# Domino_JTAG_SPI_No_Teardrop.net
KiCad netlist of a schematic drawn in EAGLE
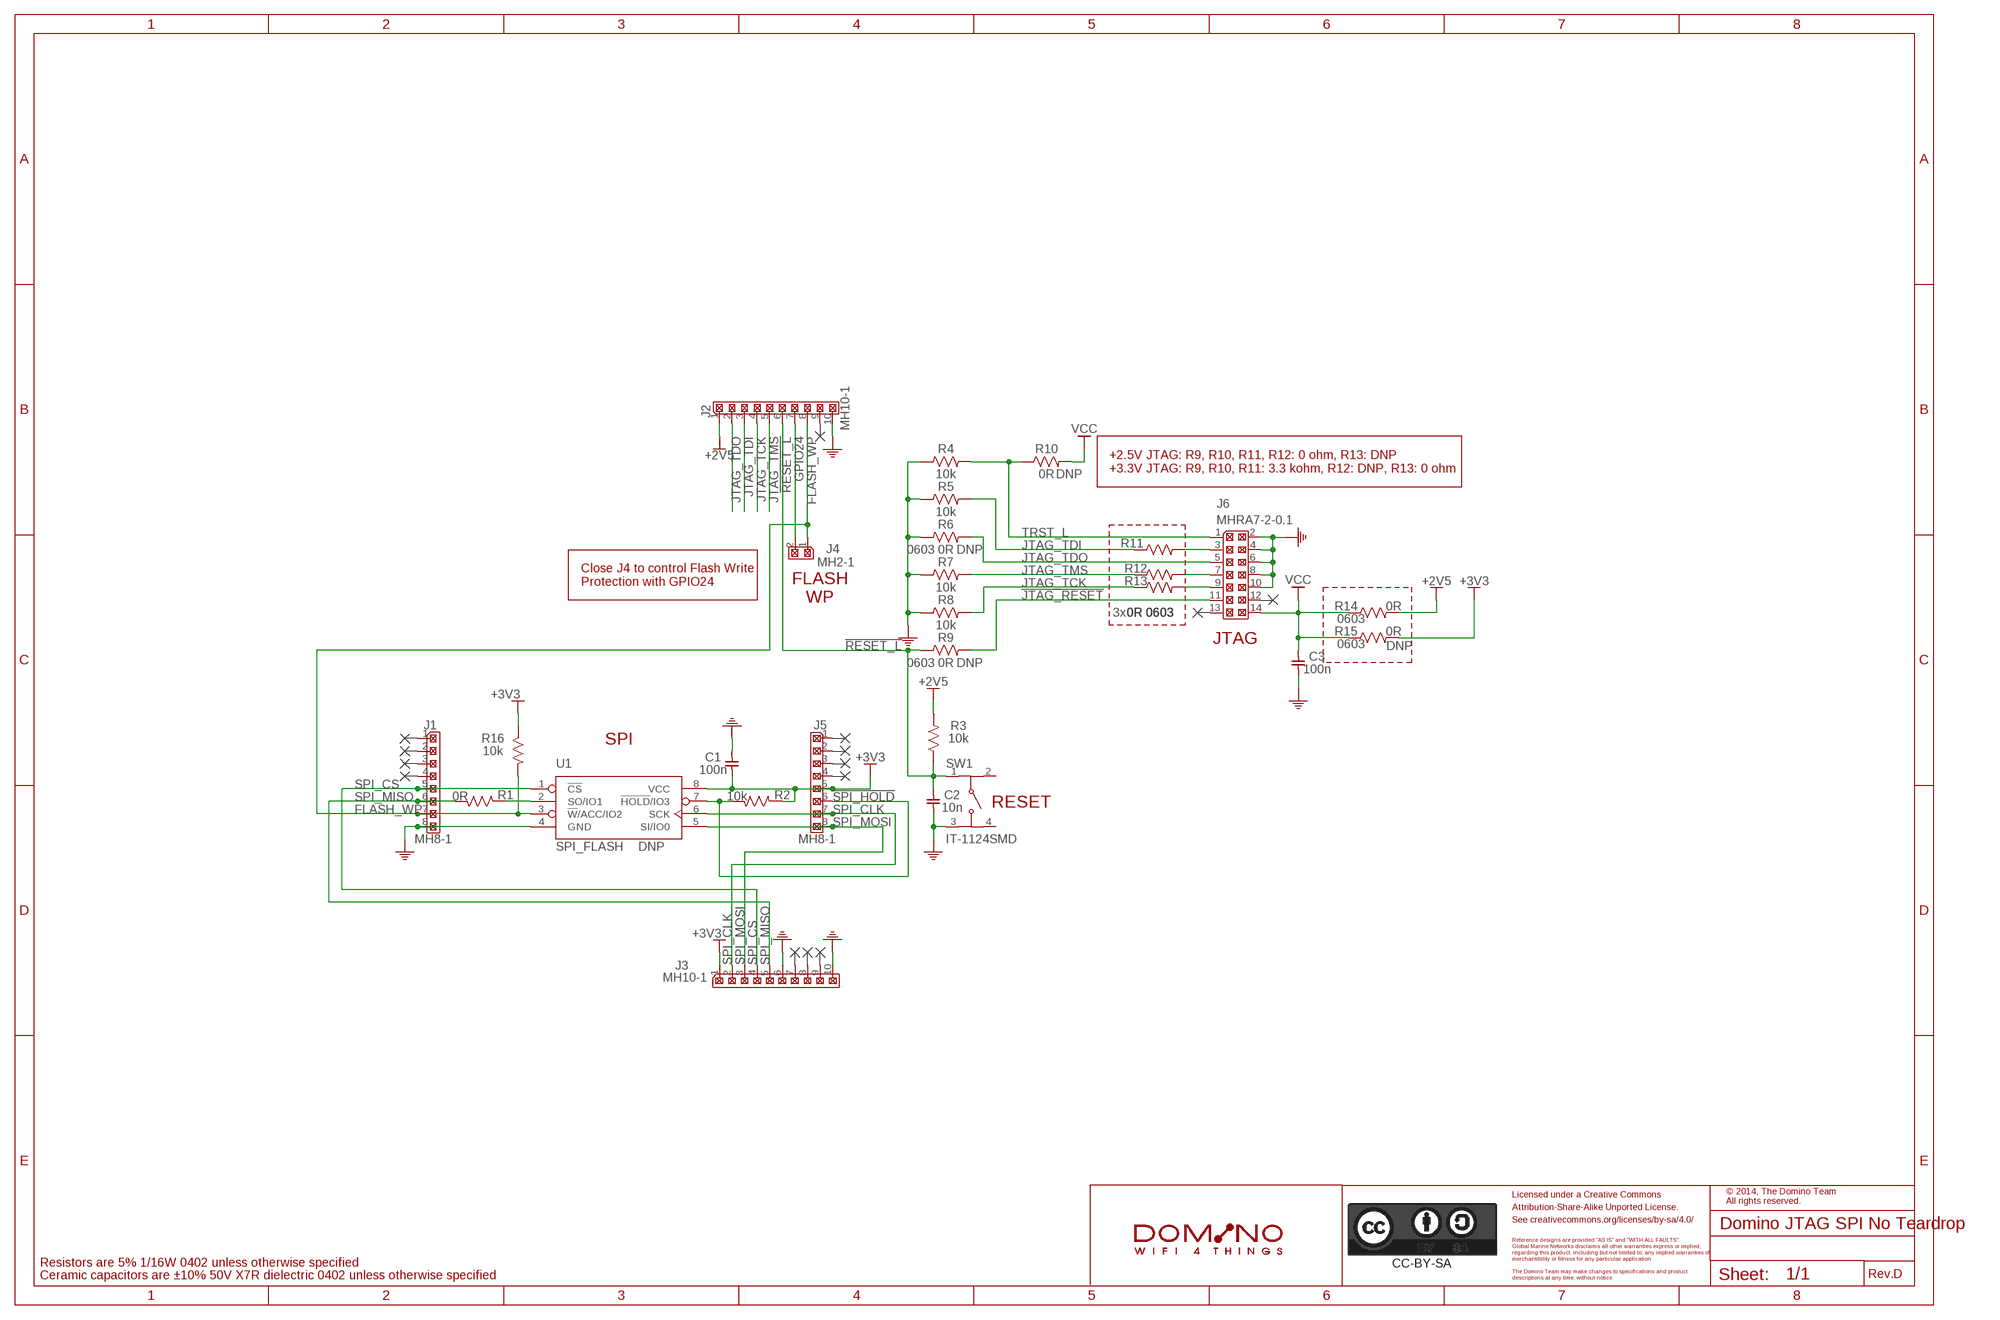
[diagram p0: schematic, sheet 1]

(export (version "E")
  (design (tool "Eeschema 10.0.6"))
  (components
    (comp (ref "C1")
      (value "100n")
      (footprint "eagle-import:C0402")
      (fields (field (name "PARTNO") "C0402_100n_X7R_10%_CER_50V"))
      (libsource (lib "eagle-import") (part "CAP_0402"))
    )
    (comp (ref "C2")
      (value "10n")
      (footprint "eagle-import:C0402")
      (fields (field (name "PARTNO") "C0402_10n_X7R_10%_CER_50V"))
      (libsource (lib "eagle-import") (part "CAP_0402"))
    )
    (comp (ref "C3")
      (value "100n")
      (footprint "eagle-import:C0402")
      (fields (field (name "PARTNO") "C0402_100n_X7R_10%_CER_50V"))
      (libsource (lib "eagle-import") (part "CAP_0402"))
    )
    (comp (ref "CC-BY-SA1")
      (value "CC-BY-SA_LOGO")
      (footprint "eagle-import:CC-BY-SA_LOGO")
      (libsource (lib "eagle-import") (part "CC-BY-SA_LOGO"))
    )
    (comp (ref "J1")
      (value "MH8-1")
      (footprint "eagle-import:MH8-1-0.1")
      (fields (field (name "PARTNO") "MH8-1-0.1"))
      (libsource (lib "eagle-import") (part "MH8-1"))
    )
    (comp (ref "J2")
      (value "MH10-1")
      (footprint "eagle-import:MH10-1-0.1")
      (fields (field (name "PARTNO") "MH10-1-0.1"))
      (libsource (lib "eagle-import") (part "MH10-1"))
    )
    (comp (ref "J3")
      (value "MH10-1")
      (footprint "eagle-import:MH10-1-0.1")
      (fields (field (name "PARTNO") "MH10-1-0.1"))
      (libsource (lib "eagle-import") (part "MH10-1"))
    )
    (comp (ref "J4")
      (value "MH2-1")
      (footprint "eagle-import:MH2-1-0.1")
      (fields (field (name "PARTNO") "MH2-1-0.1"))
      (libsource (lib "eagle-import") (part "MH2-1"))
    )
    (comp (ref "J5")
      (value "MH8-1")
      (footprint "eagle-import:MH8-1-0.1")
      (fields (field (name "PARTNO") "MH8-1-0.1"))
      (libsource (lib "eagle-import") (part "MH8-1"))
    )
    (comp (ref "J6")
      (value "MHRA7-2-0.1")
      (footprint "eagle-import:MHRA7-2-0.1")
      (libsource (lib "eagle-import") (part "MHRA7-2-0.1"))
    )
    (comp (ref "R1")
      (value "0R")
      (footprint "eagle-import:R0402")
      (fields (field (name "PARTNO") "R0402_0R_5%_62.5mW"))
      (libsource (lib "eagle-import") (part "RES_0402"))
    )
    (comp (ref "R2")
      (value "10k")
      (footprint "eagle-import:R0402")
      (fields (field (name "PARTNO") "R0402_10k_5%_62.5mW"))
      (libsource (lib "eagle-import") (part "RES_0402"))
    )
    (comp (ref "R3")
      (value "10k")
      (footprint "eagle-import:R0402")
      (fields (field (name "PARTNO") "R0402_10k_5%_62.5mW"))
      (libsource (lib "eagle-import") (part "RES_0402"))
    )
    (comp (ref "R4")
      (value "10k")
      (footprint "eagle-import:R0402")
      (fields (field (name "PARTNO") "R0402_10k_5%_62.5mW"))
      (libsource (lib "eagle-import") (part "RES_0402"))
    )
    (comp (ref "R5")
      (value "10k")
      (footprint "eagle-import:R0402")
      (fields (field (name "PARTNO") "R0402_10k_5%_62.5mW"))
      (libsource (lib "eagle-import") (part "RES_0402"))
    )
    (comp (ref "R6")
      (value "0R")
      (footprint "eagle-import:R0603")
      (fields (field (name "SIZE") "0603") (field (name "PARTNO") "R0603_0R_5%_125mW"))
      (libsource (lib "eagle-import") (part "RES_0603"))
    )
    (comp (ref "R7")
      (value "10k")
      (footprint "eagle-import:R0402")
      (fields (field (name "PARTNO") "R0402_10k_5%_62.5mW"))
      (libsource (lib "eagle-import") (part "RES_0402"))
    )
    (comp (ref "R8")
      (value "10k")
      (footprint "eagle-import:R0402")
      (fields (field (name "PARTNO") "R0402_10k_5%_62.5mW"))
      (libsource (lib "eagle-import") (part "RES_0402"))
    )
    (comp (ref "R9")
      (value "0R")
      (footprint "eagle-import:R0603")
      (fields (field (name "SIZE") "0603") (field (name "PARTNO") "R0603_0R_5%_125mW"))
      (libsource (lib "eagle-import") (part "RES_0603"))
    )
    (comp (ref "R10")
      (value "0R")
      (footprint "eagle-import:R0603")
      (fields (field (name "PARTNO") "R0603_0R_5%_125mW"))
      (libsource (lib "eagle-import") (part "RES_0603"))
    )
    (comp (ref "R11")
      (value "0R")
      (footprint "eagle-import:R0603")
      (fields (field (name "SIZE") "0603") (field (name "PARTNO") "R0603_0R_5%_125mW"))
      (libsource (lib "eagle-import") (part "RES_0603"))
    )
    (comp (ref "R12")
      (value "0R")
      (footprint "eagle-import:R0603")
      (fields (field (name "SIZE") "0603") (field (name "PARTNO") "R0603_0R_5%_125mW"))
      (libsource (lib "eagle-import") (part "RES_0603"))
    )
    (comp (ref "R13")
      (value "0R")
      (footprint "eagle-import:R0603")
      (fields (field (name "SIZE") "0603") (field (name "PARTNO") "R0603_0R_5%_125mW"))
      (libsource (lib "eagle-import") (part "RES_0603"))
    )
    (comp (ref "R14")
      (value "0R")
      (footprint "eagle-import:R0603")
      (fields (field (name "SIZE") "0603") (field (name "PARTNO") "R0603_0R_5%_125mW"))
      (libsource (lib "eagle-import") (part "RES_0603"))
    )
    (comp (ref "R15")
      (value "0R")
      (footprint "eagle-import:R0603")
      (fields (field (name "SIZE") "0603") (field (name "PARTNO") "R0603_0R_5%_125mW"))
      (libsource (lib "eagle-import") (part "RES_0603"))
    )
    (comp (ref "R16")
      (value "10k")
      (footprint "eagle-import:R0402")
      (fields (field (name "PARTNO") "R0402_10k_5%_62.5mW"))
      (libsource (lib "eagle-import") (part "RES_0402"))
    )
    (comp (ref "SW1")
      (value "IT-1124SMD")
      (footprint "eagle-import:IT-1124SMD")
      (libsource (lib "eagle-import") (part "IT-1124SMD"))
    )
    (comp (ref "U$2")
      (value "DOMINO_LOGO")
      (footprint "eagle-import:DOMINO_LOGO")
      (libsource (lib "eagle-import") (part "DOMINO_LOGO"))
    )
    (comp (ref "U1")
      (value "SPI_FLASH")
      (footprint "eagle-import:SOIC-8")
      (libsource (lib "eagle-import") (part "SPI_FLASH"))
    )
  )
  (nets
    (net (code "1") (name "+2V5") (class "Default")
      (node (ref "J2") (pin "1") (pinfunction "1_1") (pintype "passive"))
      (node (ref "R14") (pin "2") (pinfunction "2_2") (pintype "passive"))
      (node (ref "R3") (pin "2") (pinfunction "2_2") (pintype "passive"))
    )
    (net (code "2") (name "+3V3") (class "Default")
      (node (ref "C1") (pin "2") (pinfunction "2_2") (pintype "passive"))
      (node (ref "J3") (pin "1") (pinfunction "1_1") (pintype "passive"))
      (node (ref "J5") (pin "5") (pinfunction "5_5") (pintype "passive"))
      (node (ref "R15") (pin "2") (pinfunction "2_2") (pintype "passive"))
      (node (ref "R16") (pin "1") (pinfunction "1_1") (pintype "passive"))
      (node (ref "R2") (pin "1") (pinfunction "1_1") (pintype "passive"))
      (node (ref "U1") (pin "8") (pinfunction "VCC_8") (pintype "power_in"))
    )
    (net (code "3") (name "/FLASH_WP") (class "Default")
      (node (ref "J1") (pin "7") (pinfunction "7_7") (pintype "passive"))
      (node (ref "J2") (pin "8") (pinfunction "8_8") (pintype "passive"))
      (node (ref "J4") (pin "1") (pinfunction "1_1") (pintype "passive"))
      (node (ref "R16") (pin "2") (pinfunction "2_2") (pintype "passive"))
      (node (ref "U1") (pin "3") (pinfunction "~{W}/ACC/IO2_3") (pintype "bidirectional"))
    )
    (net (code "4") (name "/GPIO24") (class "Default")
      (node (ref "J2") (pin "7") (pinfunction "7_7") (pintype "passive"))
      (node (ref "J4") (pin "2") (pinfunction "2_2") (pintype "passive"))
    )
    (net (code "5") (name "/JTAG_TCK") (class "Default")
      (node (ref "J2") (pin "4") (pinfunction "4_4") (pintype "passive"))
      (node (ref "R13") (pin "1") (pinfunction "1_1") (pintype "passive"))
      (node (ref "R8") (pin "2") (pinfunction "2_2") (pintype "passive"))
    )
    (net (code "6") (name "/JTAG_TDI") (class "Default")
      (node (ref "J2") (pin "3") (pinfunction "3_3") (pintype "passive"))
      (node (ref "R11") (pin "1") (pinfunction "1_1") (pintype "passive"))
      (node (ref "R5") (pin "2") (pinfunction "2_2") (pintype "passive"))
    )
    (net (code "7") (name "/JTAG_TDO") (class "Default")
      (node (ref "J2") (pin "2") (pinfunction "2_2") (pintype "passive"))
      (node (ref "J6") (pin "5") (pinfunction "5_5") (pintype "passive"))
      (node (ref "R6") (pin "2") (pinfunction "2_2") (pintype "passive"))
    )
    (net (code "8") (name "/JTAG_TMS") (class "Default")
      (node (ref "J2") (pin "5") (pinfunction "5_5") (pintype "passive"))
      (node (ref "R12") (pin "1") (pinfunction "1_1") (pintype "passive"))
      (node (ref "R7") (pin "2") (pinfunction "2_2") (pintype "passive"))
    )
    (net (code "9") (name "/SPI_CLK") (class "Default")
      (node (ref "J3") (pin "2") (pinfunction "2_2") (pintype "passive"))
      (node (ref "J5") (pin "7") (pinfunction "7_7") (pintype "passive"))
      (node (ref "U1") (pin "6") (pinfunction "SCK_6") (pintype "input"))
    )
    (net (code "10") (name "/SPI_CS") (class "Default")
      (node (ref "J1") (pin "5") (pinfunction "5_5") (pintype "passive"))
      (node (ref "J3") (pin "4") (pinfunction "4_4") (pintype "passive"))
      (node (ref "U1") (pin "1") (pinfunction "~{CS}_1") (pintype "input"))
    )
    (net (code "11") (name "/SPI_MISO") (class "Default")
      (node (ref "J1") (pin "6") (pinfunction "6_6") (pintype "passive"))
      (node (ref "J3") (pin "5") (pinfunction "5_5") (pintype "passive"))
      (node (ref "R1") (pin "2") (pinfunction "2_2") (pintype "passive"))
    )
    (net (code "12") (name "/SPI_MOSI") (class "Default")
      (node (ref "J3") (pin "3") (pinfunction "3_3") (pintype "passive"))
      (node (ref "J5") (pin "8") (pinfunction "8_8") (pintype "passive"))
      (node (ref "U1") (pin "5") (pinfunction "SI/IO0_5") (pintype "bidirectional"))
    )
    (net (code "13") (name "/TRST_L") (class "Default")
      (node (ref "J6") (pin "1") (pinfunction "1_1") (pintype "passive"))
      (node (ref "R10") (pin "1") (pinfunction "1_1") (pintype "passive"))
      (node (ref "R4") (pin "2") (pinfunction "2_2") (pintype "passive"))
    )
    (net (code "14") (name "/~{JTAG_RESET}") (class "Default")
      (node (ref "J6") (pin "11") (pinfunction "11_11") (pintype "passive"))
      (node (ref "R9") (pin "2") (pinfunction "2_2") (pintype "passive"))
    )
    (net (code "15") (name "/~{RESET_L}") (class "Default")
      (node (ref "C2") (pin "1") (pinfunction "1_1") (pintype "passive"))
      (node (ref "J2") (pin "6") (pinfunction "6_6") (pintype "passive"))
      (node (ref "R3") (pin "1") (pinfunction "1_1") (pintype "passive"))
      (node (ref "R9") (pin "1") (pinfunction "1_1") (pintype "passive"))
      (node (ref "SW1") (pin "1") (pinfunction "1_1") (pintype "passive"))
    )
    (net (code "16") (name "/~{SPI_HOLD}") (class "Default")
      (node (ref "J5") (pin "6") (pinfunction "6_6") (pintype "passive"))
      (node (ref "R2") (pin "2") (pinfunction "2_2") (pintype "passive"))
      (node (ref "U1") (pin "7") (pinfunction "~{HOLD}/IO3_7") (pintype "bidirectional"))
    )
    (net (code "17") (name "GND") (class "Default")
      (node (ref "C1") (pin "1") (pinfunction "1_1") (pintype "passive"))
      (node (ref "C2") (pin "2") (pinfunction "2_2") (pintype "passive"))
      (node (ref "C3") (pin "2") (pinfunction "2_2") (pintype "passive"))
      (node (ref "J1") (pin "8") (pinfunction "8_8") (pintype "passive"))
      (node (ref "J2") (pin "10") (pinfunction "10_10") (pintype "passive"))
      (node (ref "J3") (pin "10") (pinfunction "10_10") (pintype "passive"))
      (node (ref "J3") (pin "6") (pinfunction "6_6") (pintype "passive"))
      (node (ref "J6") (pin "10") (pinfunction "10_10") (pintype "passive"))
      (node (ref "J6") (pin "2") (pinfunction "2_2") (pintype "passive"))
      (node (ref "J6") (pin "4") (pinfunction "4_4") (pintype "passive"))
      (node (ref "J6") (pin "6") (pinfunction "6_6") (pintype "passive"))
      (node (ref "J6") (pin "8") (pinfunction "8_8") (pintype "passive"))
      (node (ref "R4") (pin "1") (pinfunction "1_1") (pintype "passive"))
      (node (ref "R5") (pin "1") (pinfunction "1_1") (pintype "passive"))
      (node (ref "R6") (pin "1") (pinfunction "1_1") (pintype "passive"))
      (node (ref "R7") (pin "1") (pinfunction "1_1") (pintype "passive"))
      (node (ref "R8") (pin "1") (pinfunction "1_1") (pintype "passive"))
      (node (ref "SW1") (pin "3") (pinfunction "3_3") (pintype "passive"))
      (node (ref "U1") (pin "4") (pinfunction "GND_4") (pintype "power_in"))
    )
    (net (code "18") (name "Net-(J6-Pad3)") (class "Default")
      (node (ref "J6") (pin "3") (pinfunction "3_3") (pintype "passive"))
      (node (ref "R11") (pin "2") (pinfunction "2_2") (pintype "passive"))
    )
    (net (code "19") (name "Net-(J6-Pad7)") (class "Default")
      (node (ref "J6") (pin "7") (pinfunction "7_7") (pintype "passive"))
      (node (ref "R12") (pin "2") (pinfunction "2_2") (pintype "passive"))
    )
    (net (code "20") (name "Net-(J6-Pad9)") (class "Default")
      (node (ref "J6") (pin "9") (pinfunction "9_9") (pintype "passive"))
      (node (ref "R13") (pin "2") (pinfunction "2_2") (pintype "passive"))
    )
    (net (code "21") (name "Net-(U1-SO{slash}IO1)") (class "Default")
      (node (ref "R1") (pin "1") (pinfunction "1_1") (pintype "passive"))
      (node (ref "U1") (pin "2") (pinfunction "SO/IO1_2") (pintype "bidirectional"))
    )
    (net (code "22") (name "VCC") (class "Default")
      (node (ref "C3") (pin "1") (pinfunction "1_1") (pintype "passive"))
      (node (ref "J6") (pin "14") (pinfunction "14_14") (pintype "passive"))
      (node (ref "R10") (pin "2") (pinfunction "2_2") (pintype "passive"))
      (node (ref "R14") (pin "1") (pinfunction "1_1") (pintype "passive"))
      (node (ref "R15") (pin "1") (pinfunction "1_1") (pintype "passive"))
    )
    (net (code "23") (name "unconnected-(J1-Pad1)") (class "Default")
      (node (ref "J1") (pin "1") (pinfunction "1_1") (pintype "passive"))
    )
    (net (code "24") (name "unconnected-(J1-Pad2)") (class "Default")
      (node (ref "J1") (pin "2") (pinfunction "2_2") (pintype "passive"))
    )
    (net (code "25") (name "unconnected-(J1-Pad3)") (class "Default")
      (node (ref "J1") (pin "3") (pinfunction "3_3") (pintype "passive"))
    )
    (net (code "26") (name "unconnected-(J1-Pad4)") (class "Default")
      (node (ref "J1") (pin "4") (pinfunction "4_4") (pintype "passive"))
    )
    (net (code "27") (name "unconnected-(J2-Pad9)") (class "Default")
      (node (ref "J2") (pin "9") (pinfunction "9_9") (pintype "passive"))
    )
    (net (code "28") (name "unconnected-(J3-Pad7)") (class "Default")
      (node (ref "J3") (pin "7") (pinfunction "7_7") (pintype "passive"))
    )
    (net (code "29") (name "unconnected-(J3-Pad8)") (class "Default")
      (node (ref "J3") (pin "8") (pinfunction "8_8") (pintype "passive"))
    )
    (net (code "30") (name "unconnected-(J3-Pad9)") (class "Default")
      (node (ref "J3") (pin "9") (pinfunction "9_9") (pintype "passive"))
    )
    (net (code "31") (name "unconnected-(J5-Pad1)") (class "Default")
      (node (ref "J5") (pin "1") (pinfunction "1_1") (pintype "passive"))
    )
    (net (code "32") (name "unconnected-(J5-Pad2)") (class "Default")
      (node (ref "J5") (pin "2") (pinfunction "2_2") (pintype "passive"))
    )
    (net (code "33") (name "unconnected-(J5-Pad3)") (class "Default")
      (node (ref "J5") (pin "3") (pinfunction "3_3") (pintype "passive"))
    )
    (net (code "34") (name "unconnected-(J5-Pad4)") (class "Default")
      (node (ref "J5") (pin "4") (pinfunction "4_4") (pintype "passive"))
    )
    (net (code "35") (name "unconnected-(J6-Pad12)") (class "Default")
      (node (ref "J6") (pin "12") (pinfunction "12_12") (pintype "passive"))
    )
    (net (code "36") (name "unconnected-(J6-Pad13)") (class "Default")
      (node (ref "J6") (pin "13") (pinfunction "13_13") (pintype "passive"))
    )
    (net (code "37") (name "unconnected-(SW1-Pad2)") (class "Default")
      (node (ref "SW1") (pin "2") (pinfunction "2_2") (pintype "passive"))
    )
    (net (code "38") (name "unconnected-(SW1-Pad4)") (class "Default")
      (node (ref "SW1") (pin "4") (pinfunction "4_4") (pintype "passive"))
    )
  )
)
